# RcrSchemBack.net
KiCad netlist of a schematic drawn in EAGLE
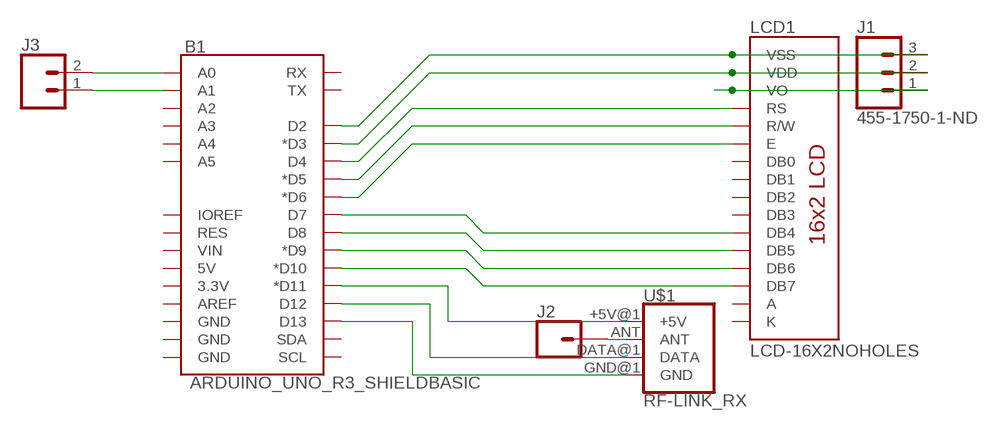
[diagram p0: schematic, sheet 1]

(export (version "E")
  (design (tool "Eeschema 10.0.6"))
  (components
    (comp (ref "B1")
      (value "ARDUINO_UNO_R3_SHIELDBASIC")
      (footprint "eagle-import:UNO_R3_SHIELD")
      (libsource (lib "eagle-import") (part "ARDUINO_UNO_R3_SHIELDBASIC"))
    )
    (comp (ref "J1")
      (value "455-1750-1-ND")
      (footprint "eagle-import:1X03")
      (libsource (lib "eagle-import") (part "CONN_03"))
    )
    (comp (ref "J2")
      (value "CONN_01")
      (footprint "eagle-import:1X01")
      (libsource (lib "eagle-import") (part "CONN_01"))
    )
    (comp (ref "J3")
      (value "CONN_02")
      (footprint "eagle-import:1X02")
      (libsource (lib "eagle-import") (part "CONN_02"))
    )
    (comp (ref "LCD1")
      (value "LCD-16X2NOHOLES")
      (footprint "eagle-import:LCD-16X2_NOHOLESNOSILK")
      (libsource (lib "eagle-import") (part "LCD-16X2NOHOLES"))
    )
    (comp (ref "U$1")
      (value "RF-LINK_RX")
      (footprint "eagle-import:RF-LINK_RX")
      (libsource (lib "eagle-import") (part "RF-LINK_RX"))
    )
  )
  (nets
    (net (code "1") (name "/A") (class "Default")
      (node (ref "LCD1") (pin "15") (pinfunction "A_15") (pintype "power_in"))
    )
    (net (code "2") (name "/K") (class "Default")
      (node (ref "LCD1") (pin "16") (pinfunction "K_16") (pintype "power_in"))
    )
    (net (code "3") (name "Net-(B1-*D3)") (class "Default")
      (node (ref "B1") (pin "D3") (pinfunction "*D3_D3") (pintype "bidirectional"))
      (node (ref "J1") (pin "2") (pinfunction "2_2") (pintype "passive"))
      (node (ref "LCD1") (pin "2") (pinfunction "VDD_2") (pintype "power_in"))
    )
    (net (code "4") (name "Net-(B1-*D5)") (class "Default")
      (node (ref "B1") (pin "D5") (pinfunction "*D5_D5") (pintype "bidirectional"))
      (node (ref "LCD1") (pin "5") (pinfunction "R/W_5") (pintype "input"))
    )
    (net (code "5") (name "Net-(B1-*D6)") (class "Default")
      (node (ref "B1") (pin "D6") (pinfunction "*D6_D6") (pintype "bidirectional"))
      (node (ref "LCD1") (pin "6") (pinfunction "E_6") (pintype "input"))
    )
    (net (code "6") (name "Net-(B1-*D9)") (class "Default")
      (node (ref "B1") (pin "D9") (pinfunction "*D9_D9") (pintype "bidirectional"))
      (node (ref "LCD1") (pin "13") (pinfunction "DB6_13") (pintype "bidirectional"))
    )
    (net (code "7") (name "Net-(B1-*D10)") (class "Default")
      (node (ref "B1") (pin "D10") (pinfunction "*D10_D10") (pintype "bidirectional"))
      (node (ref "LCD1") (pin "14") (pinfunction "DB7_14") (pintype "bidirectional"))
    )
    (net (code "8") (name "Net-(B1-*D11)") (class "Default")
      (node (ref "B1") (pin "D11") (pinfunction "*D11_D11") (pintype "bidirectional"))
      (node (ref "U$1") (pin "+5V@1") (pinfunction "+5V_+5V@1") (pintype "power_in"))
    )
    (net (code "9") (name "Net-(B1-PadA0)") (class "Default")
      (node (ref "B1") (pin "A0") (pinfunction "A0_A0") (pintype "bidirectional"))
      (node (ref "J3") (pin "2") (pinfunction "2_2") (pintype "passive"))
    )
    (net (code "10") (name "Net-(B1-PadA1)") (class "Default")
      (node (ref "B1") (pin "A1") (pinfunction "A1_A1") (pintype "bidirectional"))
      (node (ref "J3") (pin "1") (pinfunction "1_1") (pintype "passive"))
    )
    (net (code "11") (name "Net-(J2-Pad1)") (class "Default")
      (node (ref "J2") (pin "1") (pinfunction "1_1") (pintype "passive"))
      (node (ref "U$1") (pin "ANT") (pinfunction "ANT_ANT") (pintype "passive"))
    )
    (net (code "12") (name "Net-(LCD1-DB4)") (class "Default")
      (node (ref "B1") (pin "D7") (pinfunction "D7_D7") (pintype "bidirectional"))
      (node (ref "LCD1") (pin "11") (pinfunction "DB4_11") (pintype "bidirectional"))
    )
    (net (code "13") (name "Net-(LCD1-DB5)") (class "Default")
      (node (ref "B1") (pin "D8") (pinfunction "D8_D8") (pintype "bidirectional"))
      (node (ref "LCD1") (pin "12") (pinfunction "DB5_12") (pintype "bidirectional"))
    )
    (net (code "14") (name "Net-(LCD1-RS)") (class "Default")
      (node (ref "B1") (pin "D4") (pinfunction "D4_D4") (pintype "bidirectional"))
      (node (ref "LCD1") (pin "4") (pinfunction "RS_4") (pintype "input"))
    )
    (net (code "15") (name "Net-(LCD1-VO)") (class "Default")
      (node (ref "J1") (pin "1") (pinfunction "1_1") (pintype "passive"))
      (node (ref "LCD1") (pin "3") (pinfunction "VO_3") (pintype "bidirectional"))
    )
    (net (code "16") (name "Net-(LCD1-VSS)") (class "Default")
      (node (ref "B1") (pin "D2") (pinfunction "D2_D2") (pintype "bidirectional"))
      (node (ref "J1") (pin "3") (pinfunction "3_3") (pintype "passive"))
      (node (ref "LCD1") (pin "1") (pinfunction "VSS_1") (pintype "power_in"))
    )
    (net (code "17") (name "Net-(U$1-DATA)") (class "Default")
      (node (ref "B1") (pin "D12") (pinfunction "D12_D12") (pintype "bidirectional"))
      (node (ref "U$1") (pin "DATA@1") (pinfunction "DATA_DATA@1") (pintype "input"))
    )
    (net (code "18") (name "Net-(U$1-GND)") (class "Default")
      (node (ref "B1") (pin "D13") (pinfunction "D13_D13") (pintype "bidirectional"))
      (node (ref "U$1") (pin "GND@1") (pinfunction "GND_GND@1") (pintype "power_in"))
    )
    (net (code "19") (name "unconnected-(B1-GND-PadGND@0)") (class "Default")
      (node (ref "B1") (pin "GND@0") (pinfunction "GND_GND@0") (pintype "bidirectional"))
    )
    (net (code "20") (name "unconnected-(B1-GND-PadGND@1)") (class "Default")
      (node (ref "B1") (pin "GND@1") (pinfunction "GND_GND@1") (pintype "bidirectional"))
    )
    (net (code "21") (name "unconnected-(B1-GND-PadGND@2)") (class "Default")
      (node (ref "B1") (pin "GND@2") (pinfunction "GND_GND@2") (pintype "bidirectional"))
    )
    (net (code "22") (name "unconnected-(B1-Pad3.3V)") (class "Default")
      (node (ref "B1") (pin "3.3V") (pinfunction "3.3V_3.3V") (pintype "bidirectional"))
    )
    (net (code "23") (name "unconnected-(B1-Pad5V)") (class "Default")
      (node (ref "B1") (pin "5V") (pinfunction "5V_5V") (pintype "bidirectional"))
    )
    (net (code "24") (name "unconnected-(B1-PadA2)") (class "Default")
      (node (ref "B1") (pin "A2") (pinfunction "A2_A2") (pintype "bidirectional"))
    )
    (net (code "25") (name "unconnected-(B1-PadA3)") (class "Default")
      (node (ref "B1") (pin "A3") (pinfunction "A3_A3") (pintype "bidirectional"))
    )
    (net (code "26") (name "unconnected-(B1-PadA4)") (class "Default")
      (node (ref "B1") (pin "A4") (pinfunction "A4_A4") (pintype "bidirectional"))
    )
    (net (code "27") (name "unconnected-(B1-PadA5)") (class "Default")
      (node (ref "B1") (pin "A5") (pinfunction "A5_A5") (pintype "bidirectional"))
    )
    (net (code "28") (name "unconnected-(B1-PadAREF)") (class "Default")
      (node (ref "B1") (pin "AREF") (pinfunction "AREF_AREF") (pintype "bidirectional"))
    )
    (net (code "29") (name "unconnected-(B1-PadIOREF)") (class "Default")
      (node (ref "B1") (pin "IOREF") (pinfunction "IOREF_IOREF") (pintype "bidirectional"))
    )
    (net (code "30") (name "unconnected-(B1-PadRES)") (class "Default")
      (node (ref "B1") (pin "RES") (pinfunction "RES_RES") (pintype "bidirectional"))
    )
    (net (code "31") (name "unconnected-(B1-PadRX)") (class "Default")
      (node (ref "B1") (pin "RX") (pinfunction "RX_RX") (pintype "bidirectional"))
    )
    (net (code "32") (name "unconnected-(B1-PadSCL)") (class "Default")
      (node (ref "B1") (pin "SCL") (pinfunction "SCL_SCL") (pintype "bidirectional"))
    )
    (net (code "33") (name "unconnected-(B1-PadSDA)") (class "Default")
      (node (ref "B1") (pin "SDA") (pinfunction "SDA_SDA") (pintype "bidirectional"))
    )
    (net (code "34") (name "unconnected-(B1-PadTX)") (class "Default")
      (node (ref "B1") (pin "TX") (pinfunction "TX_TX") (pintype "bidirectional"))
    )
    (net (code "35") (name "unconnected-(B1-PadVIN)") (class "Default")
      (node (ref "B1") (pin "VIN") (pinfunction "VIN_VIN") (pintype "bidirectional"))
    )
    (net (code "36") (name "unconnected-(LCD1-DB0-Pad7)") (class "Default")
      (node (ref "LCD1") (pin "7") (pinfunction "DB0_7") (pintype "bidirectional"))
    )
    (net (code "37") (name "unconnected-(LCD1-DB1-Pad8)") (class "Default")
      (node (ref "LCD1") (pin "8") (pinfunction "DB1_8") (pintype "bidirectional"))
    )
    (net (code "38") (name "unconnected-(LCD1-DB2-Pad9)") (class "Default")
      (node (ref "LCD1") (pin "9") (pinfunction "DB2_9") (pintype "bidirectional"))
    )
    (net (code "39") (name "unconnected-(LCD1-DB3-Pad10)") (class "Default")
      (node (ref "LCD1") (pin "10") (pinfunction "DB3_10") (pintype "bidirectional"))
    )
  )
)
